# remote.net
KiCad netlist of a schematic drawn in EAGLE
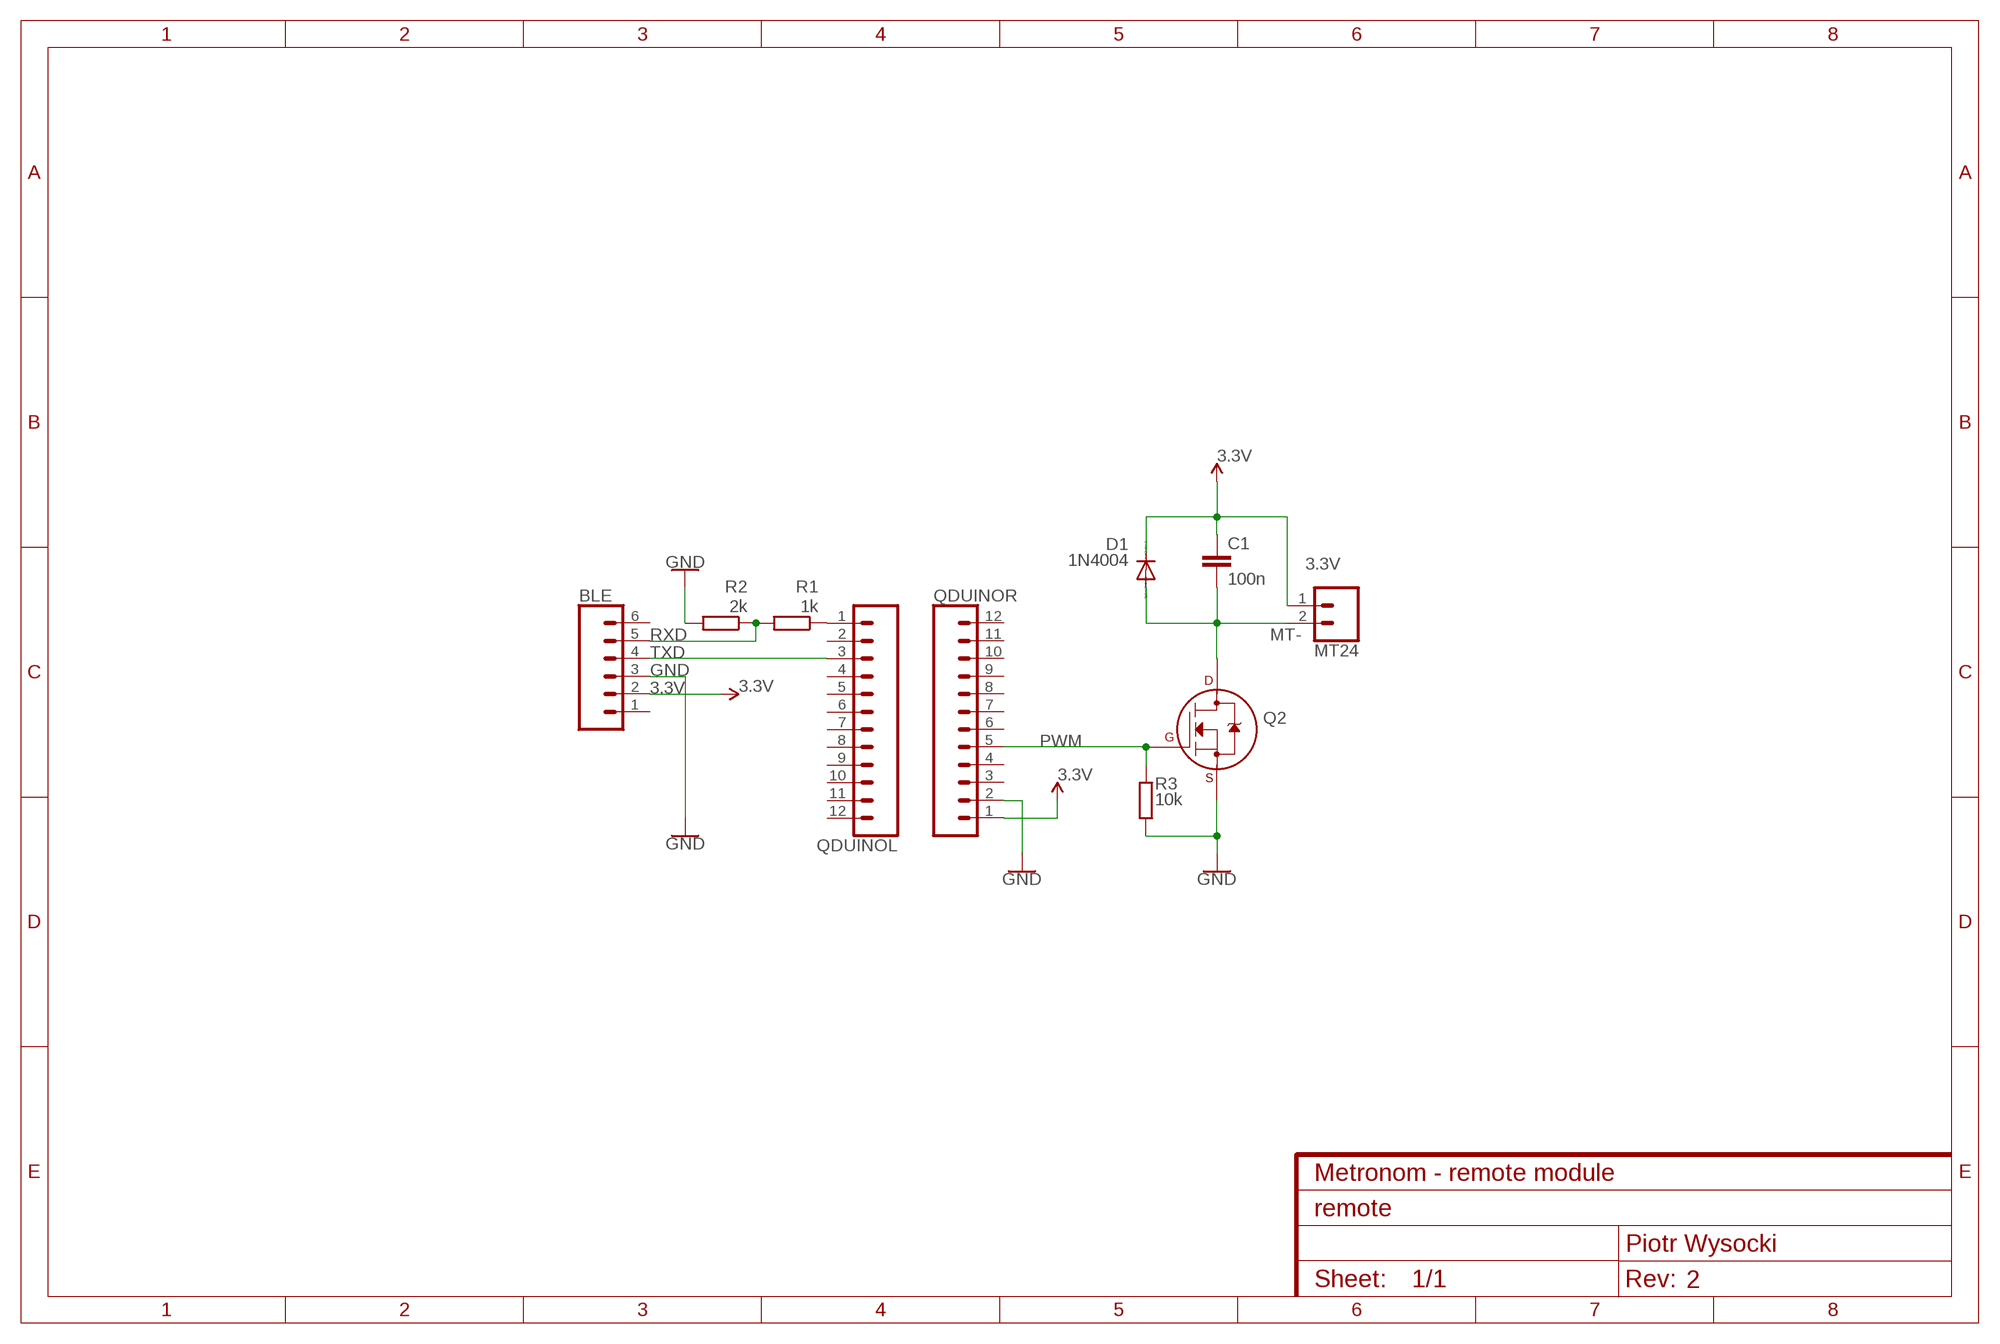
[diagram p0: schematic, sheet 1]

(export (version "E")
  (design (tool "Eeschema 10.0.6"))
  (components
    (comp (ref "BLE")
      (value "CONN_06SILK_FEMALE_PTH")
      (footprint "eagle-import:1X06")
      (libsource (lib "eagle-import") (part "CONN_06SILK_FEMALE_PTH"))
    )
    (comp (ref "C1")
      (value "100n")
      (footprint "eagle-import:C025-024X044")
      (libsource (lib "eagle-import") (part "C-EU025-024X044"))
    )
    (comp (ref "D1")
      (value "1N4004")
      (footprint "eagle-import:DO41-10")
      (libsource (lib "eagle-import") (part "1N4004"))
    )
    (comp (ref "MT24")
      (value "CONN_02")
      (footprint "eagle-import:1X02")
      (libsource (lib "eagle-import") (part "CONN_02"))
    )
    (comp (ref "Q2")
      (value "2N7000_TO92")
      (footprint "eagle-import:TO-92")
      (libsource (lib "eagle-import") (part "2N700_TO920"))
    )
    (comp (ref "QDUINOL")
      (value "CONN_12")
      (footprint "eagle-import:1X12")
      (libsource (lib "eagle-import") (part "CONN_12"))
    )
    (comp (ref "QDUINOR")
      (value "CONN_12")
      (footprint "eagle-import:1X12")
      (libsource (lib "eagle-import") (part "CONN_12"))
    )
    (comp (ref "R1")
      (value "1k")
      (footprint "eagle-import:0204_7")
      (libsource (lib "eagle-import") (part "R-EU_0204/7"))
    )
    (comp (ref "R2")
      (value "2k")
      (footprint "eagle-import:0204_7")
      (libsource (lib "eagle-import") (part "R-EU_0204/7"))
    )
    (comp (ref "R3")
      (value "10k")
      (footprint "eagle-import:0204_7")
      (libsource (lib "eagle-import") (part "R-EU_0204/7"))
    )
  )
  (nets
    (net (code "1") (name "/MT-") (class "Default")
      (node (ref "C1") (pin "2") (pinfunction "2_2") (pintype "passive"))
      (node (ref "D1") (pin "A") (pinfunction "A_A") (pintype "passive"))
      (node (ref "MT24") (pin "2") (pinfunction "2_2") (pintype "passive"))
      (node (ref "Q2") (pin "3") (pinfunction "D_3") (pintype "bidirectional"))
    )
    (net (code "2") (name "/PWM") (class "Default")
      (node (ref "Q2") (pin "2") (pinfunction "G_2") (pintype "tri_state"))
      (node (ref "QDUINOR") (pin "5") (pinfunction "5_5") (pintype "passive"))
      (node (ref "R3") (pin "1") (pinfunction "1_1") (pintype "passive"))
    )
    (net (code "3") (name "/RXD") (class "Default")
      (node (ref "BLE") (pin "5") (pinfunction "5_5") (pintype "passive"))
      (node (ref "R1") (pin "2") (pinfunction "2_2") (pintype "passive"))
      (node (ref "R2") (pin "1") (pinfunction "1_1") (pintype "passive"))
    )
    (net (code "4") (name "/TXD") (class "Default")
      (node (ref "BLE") (pin "4") (pinfunction "4_4") (pintype "passive"))
      (node (ref "QDUINOL") (pin "3") (pinfunction "3_3") (pintype "passive"))
    )
    (net (code "5") (name "3.3V") (class "Default")
      (node (ref "BLE") (pin "2") (pinfunction "2_2") (pintype "passive"))
      (node (ref "C1") (pin "1") (pinfunction "1_1") (pintype "passive"))
      (node (ref "D1") (pin "C") (pinfunction "C_C") (pintype "passive"))
      (node (ref "MT24") (pin "1") (pinfunction "1_1") (pintype "passive"))
      (node (ref "QDUINOR") (pin "1") (pinfunction "1_1") (pintype "passive"))
    )
    (net (code "6") (name "GND") (class "Default")
      (node (ref "BLE") (pin "3") (pinfunction "3_3") (pintype "passive"))
      (node (ref "Q2") (pin "1") (pinfunction "S_1") (pintype "bidirectional"))
      (node (ref "QDUINOR") (pin "2") (pinfunction "2_2") (pintype "passive"))
      (node (ref "R2") (pin "2") (pinfunction "2_2") (pintype "passive"))
      (node (ref "R3") (pin "2") (pinfunction "2_2") (pintype "passive"))
    )
    (net (code "7") (name "Net-(QDUINOL-Pad1)") (class "Default")
      (node (ref "QDUINOL") (pin "1") (pinfunction "1_1") (pintype "passive"))
      (node (ref "R1") (pin "1") (pinfunction "1_1") (pintype "passive"))
    )
    (net (code "8") (name "unconnected-(BLE-Pad1)") (class "Default")
      (node (ref "BLE") (pin "1") (pinfunction "1_1") (pintype "passive"))
    )
    (net (code "9") (name "unconnected-(BLE-Pad6)") (class "Default")
      (node (ref "BLE") (pin "6") (pinfunction "6_6") (pintype "passive"))
    )
    (net (code "10") (name "unconnected-(QDUINOL-Pad2)") (class "Default")
      (node (ref "QDUINOL") (pin "2") (pinfunction "2_2") (pintype "passive"))
    )
    (net (code "11") (name "unconnected-(QDUINOL-Pad4)") (class "Default")
      (node (ref "QDUINOL") (pin "4") (pinfunction "4_4") (pintype "passive"))
    )
    (net (code "12") (name "unconnected-(QDUINOL-Pad5)") (class "Default")
      (node (ref "QDUINOL") (pin "5") (pinfunction "5_5") (pintype "passive"))
    )
    (net (code "13") (name "unconnected-(QDUINOL-Pad6)") (class "Default")
      (node (ref "QDUINOL") (pin "6") (pinfunction "6_6") (pintype "passive"))
    )
    (net (code "14") (name "unconnected-(QDUINOL-Pad7)") (class "Default")
      (node (ref "QDUINOL") (pin "7") (pinfunction "7_7") (pintype "passive"))
    )
    (net (code "15") (name "unconnected-(QDUINOL-Pad8)") (class "Default")
      (node (ref "QDUINOL") (pin "8") (pinfunction "8_8") (pintype "passive"))
    )
    (net (code "16") (name "unconnected-(QDUINOL-Pad9)") (class "Default")
      (node (ref "QDUINOL") (pin "9") (pinfunction "9_9") (pintype "passive"))
    )
    (net (code "17") (name "unconnected-(QDUINOL-Pad10)") (class "Default")
      (node (ref "QDUINOL") (pin "10") (pinfunction "10_10") (pintype "passive"))
    )
    (net (code "18") (name "unconnected-(QDUINOL-Pad11)") (class "Default")
      (node (ref "QDUINOL") (pin "11") (pinfunction "11_11") (pintype "passive"))
    )
    (net (code "19") (name "unconnected-(QDUINOL-Pad12)") (class "Default")
      (node (ref "QDUINOL") (pin "12") (pinfunction "12_12") (pintype "passive"))
    )
    (net (code "20") (name "unconnected-(QDUINOR-Pad3)") (class "Default")
      (node (ref "QDUINOR") (pin "3") (pinfunction "3_3") (pintype "passive"))
    )
    (net (code "21") (name "unconnected-(QDUINOR-Pad4)") (class "Default")
      (node (ref "QDUINOR") (pin "4") (pinfunction "4_4") (pintype "passive"))
    )
    (net (code "22") (name "unconnected-(QDUINOR-Pad6)") (class "Default")
      (node (ref "QDUINOR") (pin "6") (pinfunction "6_6") (pintype "passive"))
    )
    (net (code "23") (name "unconnected-(QDUINOR-Pad7)") (class "Default")
      (node (ref "QDUINOR") (pin "7") (pinfunction "7_7") (pintype "passive"))
    )
    (net (code "24") (name "unconnected-(QDUINOR-Pad8)") (class "Default")
      (node (ref "QDUINOR") (pin "8") (pinfunction "8_8") (pintype "passive"))
    )
    (net (code "25") (name "unconnected-(QDUINOR-Pad9)") (class "Default")
      (node (ref "QDUINOR") (pin "9") (pinfunction "9_9") (pintype "passive"))
    )
    (net (code "26") (name "unconnected-(QDUINOR-Pad10)") (class "Default")
      (node (ref "QDUINOR") (pin "10") (pinfunction "10_10") (pintype "passive"))
    )
    (net (code "27") (name "unconnected-(QDUINOR-Pad11)") (class "Default")
      (node (ref "QDUINOR") (pin "11") (pinfunction "11_11") (pintype "passive"))
    )
    (net (code "28") (name "unconnected-(QDUINOR-Pad12)") (class "Default")
      (node (ref "QDUINOR") (pin "12") (pinfunction "12_12") (pintype "passive"))
    )
  )
)
